# AMS_Slave_Balancing.net
KiCad netlist of a schematic drawn in Altium Designer
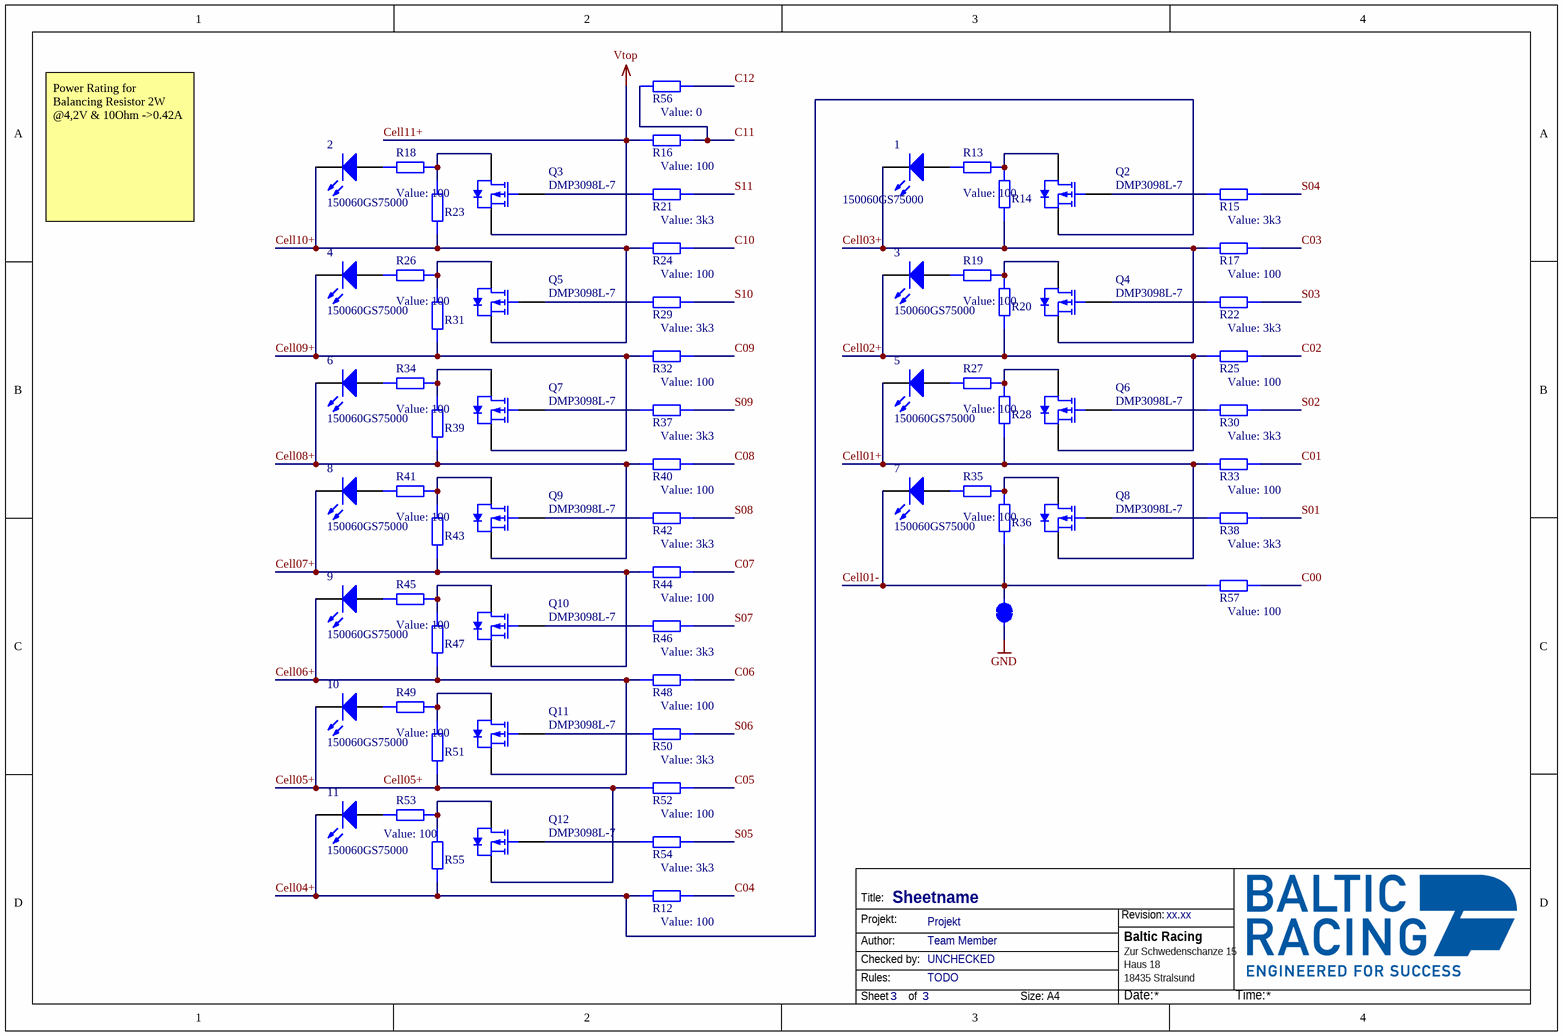
[diagram p0: AMS_Slave_Balancing.SchDoc]

(export (version "E")
  (design (tool "Eeschema 10.0.6"))
  (components
    (comp (ref "1")
      (value "150060GS75000")
      (footprint "0603_A")
      (description "SMD mono-color Chip LED, WL-SMCW, Green")
      (fields (field (name "MANUFACTURER") "Wuerth Elektronik"))
      (libsource (lib "Altium Content Vault") (part "WE-LED_K1A2-2"))
    )
    (comp (ref "2")
      (value "150060GS75000")
      (footprint "0603_A")
      (description "SMD mono-color Chip LED, WL-SMCW, Green")
      (fields (field (name "MANUFACTURER") "Wuerth Elektronik"))
      (libsource (lib "Altium Content Vault") (part "WE-LED_K1A2-2"))
    )
    (comp (ref "3")
      (value "150060GS75000")
      (footprint "0603_A")
      (description "SMD mono-color Chip LED, WL-SMCW, Green")
      (fields (field (name "MANUFACTURER") "Wuerth Elektronik"))
      (libsource (lib "Altium Content Vault") (part "WE-LED_K1A2-2"))
    )
    (comp (ref "4")
      (value "150060GS75000")
      (footprint "0603_A")
      (description "SMD mono-color Chip LED, WL-SMCW, Green")
      (fields (field (name "MANUFACTURER") "Wuerth Elektronik"))
      (libsource (lib "Altium Content Vault") (part "WE-LED_K1A2-2"))
    )
    (comp (ref "5")
      (value "150060GS75000")
      (footprint "0603_A")
      (description "SMD mono-color Chip LED, WL-SMCW, Green")
      (fields (field (name "MANUFACTURER") "Wuerth Elektronik"))
      (libsource (lib "Altium Content Vault") (part "WE-LED_K1A2-2"))
    )
    (comp (ref "6")
      (value "150060GS75000")
      (footprint "0603_A")
      (description "SMD mono-color Chip LED, WL-SMCW, Green")
      (fields (field (name "MANUFACTURER") "Wuerth Elektronik"))
      (libsource (lib "Altium Content Vault") (part "WE-LED_K1A2-2"))
    )
    (comp (ref "7")
      (value "150060GS75000")
      (footprint "0603_A")
      (description "SMD mono-color Chip LED, WL-SMCW, Green")
      (fields (field (name "MANUFACTURER") "Wuerth Elektronik"))
      (libsource (lib "Altium Content Vault") (part "WE-LED_K1A2-2"))
    )
    (comp (ref "8")
      (value "150060GS75000")
      (footprint "0603_A")
      (description "SMD mono-color Chip LED, WL-SMCW, Green")
      (fields (field (name "MANUFACTURER") "Wuerth Elektronik"))
      (libsource (lib "Altium Content Vault") (part "WE-LED_K1A2-2"))
    )
    (comp (ref "9")
      (value "150060GS75000")
      (footprint "0603_A")
      (description "SMD mono-color Chip LED, WL-SMCW, Green")
      (fields (field (name "MANUFACTURER") "Wuerth Elektronik"))
      (libsource (lib "Altium Content Vault") (part "WE-LED_K1A2-2"))
    )
    (comp (ref "10")
      (value "150060GS75000")
      (footprint "0603_A")
      (description "SMD mono-color Chip LED, WL-SMCW, Green")
      (fields (field (name "MANUFACTURER") "Wuerth Elektronik"))
      (libsource (lib "Altium Content Vault") (part "WE-LED_K1A2-2"))
    )
    (comp (ref "11")
      (value "150060GS75000")
      (footprint "0603_A")
      (description "SMD mono-color Chip LED, WL-SMCW, Green")
      (fields (field (name "MANUFACTURER") "Wuerth Elektronik"))
      (libsource (lib "Altium Content Vault") (part "WE-LED_K1A2-2"))
    )
    (comp (ref "J5")
      (value "SMD Jumper closed")
      (footprint "SMD-JUMPER-CLOSED")
      (libsource (lib "Standardbauteile") (part "SMD Jumper closed"))
    )
    (comp (ref "Q2")
      (value "DMP3098L-7")
      (footprint "DIOD-SOT23-3_V")
      (description "P-Channel Enhancement Mode MOSFET, -30 V VDS, -55 to 155 degC, 3-Pin SOT23, RoHS, Tape and Reel")
      (fields (field (name "MANUFACTURER") "Diodes Inc"))
      (libsource (lib "Altium Content Vault") (part "DIOD-PEMOS-G1S2D3-3"))
    )
    (comp (ref "Q3")
      (value "DMP3098L-7")
      (footprint "DIOD-SOT23-3_V")
      (description "P-Channel Enhancement Mode MOSFET, -30 V VDS, -55 to 155 degC, 3-Pin SOT23, RoHS, Tape and Reel")
      (fields (field (name "MANUFACTURER") "Diodes Inc"))
      (libsource (lib "Altium Content Vault") (part "DIOD-PEMOS-G1S2D3-3"))
    )
    (comp (ref "Q4")
      (value "DMP3098L-7")
      (footprint "DIOD-SOT23-3_V")
      (description "P-Channel Enhancement Mode MOSFET, -30 V VDS, -55 to 155 degC, 3-Pin SOT23, RoHS, Tape and Reel")
      (fields (field (name "MANUFACTURER") "Diodes Inc"))
      (libsource (lib "Altium Content Vault") (part "DIOD-PEMOS-G1S2D3-3"))
    )
    (comp (ref "Q5")
      (value "DMP3098L-7")
      (footprint "DIOD-SOT23-3_V")
      (description "P-Channel Enhancement Mode MOSFET, -30 V VDS, -55 to 155 degC, 3-Pin SOT23, RoHS, Tape and Reel")
      (fields (field (name "MANUFACTURER") "Diodes Inc"))
      (libsource (lib "Altium Content Vault") (part "DIOD-PEMOS-G1S2D3-3"))
    )
    (comp (ref "Q6")
      (value "DMP3098L-7")
      (footprint "DIOD-SOT23-3_V")
      (description "P-Channel Enhancement Mode MOSFET, -30 V VDS, -55 to 155 degC, 3-Pin SOT23, RoHS, Tape and Reel")
      (fields (field (name "MANUFACTURER") "Diodes Inc"))
      (libsource (lib "Altium Content Vault") (part "DIOD-PEMOS-G1S2D3-3"))
    )
    (comp (ref "Q7")
      (value "DMP3098L-7")
      (footprint "DIOD-SOT23-3_V")
      (description "P-Channel Enhancement Mode MOSFET, -30 V VDS, -55 to 155 degC, 3-Pin SOT23, RoHS, Tape and Reel")
      (fields (field (name "MANUFACTURER") "Diodes Inc"))
      (libsource (lib "Altium Content Vault") (part "DIOD-PEMOS-G1S2D3-3"))
    )
    (comp (ref "Q8")
      (value "DMP3098L-7")
      (footprint "DIOD-SOT23-3_V")
      (description "P-Channel Enhancement Mode MOSFET, -30 V VDS, -55 to 155 degC, 3-Pin SOT23, RoHS, Tape and Reel")
      (fields (field (name "MANUFACTURER") "Diodes Inc"))
      (libsource (lib "Altium Content Vault") (part "DIOD-PEMOS-G1S2D3-3"))
    )
    (comp (ref "Q9")
      (value "DMP3098L-7")
      (footprint "DIOD-SOT23-3_V")
      (description "P-Channel Enhancement Mode MOSFET, -30 V VDS, -55 to 155 degC, 3-Pin SOT23, RoHS, Tape and Reel")
      (fields (field (name "MANUFACTURER") "Diodes Inc"))
      (libsource (lib "Altium Content Vault") (part "DIOD-PEMOS-G1S2D3-3"))
    )
    (comp (ref "Q10")
      (value "DMP3098L-7")
      (footprint "DIOD-SOT23-3_V")
      (description "P-Channel Enhancement Mode MOSFET, -30 V VDS, -55 to 155 degC, 3-Pin SOT23, RoHS, Tape and Reel")
      (fields (field (name "MANUFACTURER") "Diodes Inc"))
      (libsource (lib "Altium Content Vault") (part "DIOD-PEMOS-G1S2D3-3"))
    )
    (comp (ref "Q11")
      (value "DMP3098L-7")
      (footprint "DIOD-SOT23-3_V")
      (description "P-Channel Enhancement Mode MOSFET, -30 V VDS, -55 to 155 degC, 3-Pin SOT23, RoHS, Tape and Reel")
      (fields (field (name "MANUFACTURER") "Diodes Inc"))
      (libsource (lib "Altium Content Vault") (part "DIOD-PEMOS-G1S2D3-3"))
    )
    (comp (ref "Q12")
      (value "DMP3098L-7")
      (footprint "DIOD-SOT23-3_V")
      (description "P-Channel Enhancement Mode MOSFET, -30 V VDS, -55 to 155 degC, 3-Pin SOT23, RoHS, Tape and Reel")
      (fields (field (name "MANUFACTURER") "Diodes Inc"))
      (libsource (lib "Altium Content Vault") (part "DIOD-PEMOS-G1S2D3-3"))
    )
    (comp (ref "R12")
      (value "100")
      (footprint "STACKPOLE CSR0603")
      (description "Resistor with multiple footprints")
      (fields (field (name "Comment") "Value"))
      (libsource (lib "Standardbauteile") (part "SMD Resistor"))
    )
    (comp (ref "R13")
      (value "100")
      (footprint "STACKPOLE CSR0603")
      (description "Resistor with multiple footprints")
      (fields (field (name "Comment") "SMD Resistor"))
      (libsource (lib "") (part "SMD Resistor_1"))
    )
    (comp (ref "R14")
      (value "SMD Resistor")
      (footprint "STACKPOLE CSRN2512")
      (description "Resistor with multiple footprints")
      (libsource (lib "Standardbauteile") (part "SMD Resistor"))
    )
    (comp (ref "R15")
      (value "3k3")
      (footprint "STACKPOLE CSR0603")
      (description "Resistor with multiple footprints")
      (fields (field (name "Comment") "SMD Resistor"))
      (libsource (lib "Standardbauteile") (part "SMD Resistor"))
    )
    (comp (ref "R16")
      (value "100")
      (footprint "STACKPOLE CSR0603")
      (description "Resistor with multiple footprints")
      (fields (field (name "Comment") "Value"))
      (libsource (lib "Standardbauteile") (part "SMD Resistor"))
    )
    (comp (ref "R17")
      (value "100")
      (footprint "STACKPOLE CSR0603")
      (description "Resistor with multiple footprints")
      (fields (field (name "Comment") "Value"))
      (libsource (lib "Standardbauteile") (part "SMD Resistor"))
    )
    (comp (ref "R18")
      (value "100")
      (footprint "STACKPOLE CSR0603")
      (description "Resistor with multiple footprints")
      (fields (field (name "Comment") "SMD Resistor"))
      (libsource (lib "") (part "SMD Resistor_1"))
    )
    (comp (ref "R19")
      (value "100")
      (footprint "STACKPOLE CSR0603")
      (description "Resistor with multiple footprints")
      (fields (field (name "Comment") "SMD Resistor"))
      (libsource (lib "") (part "SMD Resistor_1"))
    )
    (comp (ref "R20")
      (value "SMD Resistor")
      (footprint "STACKPOLE CSRN2512")
      (description "Resistor with multiple footprints")
      (libsource (lib "Standardbauteile") (part "SMD Resistor"))
    )
    (comp (ref "R21")
      (value "3k3")
      (footprint "STACKPOLE CSR0603")
      (description "Resistor with multiple footprints")
      (fields (field (name "Comment") "SMD Resistor"))
      (libsource (lib "Standardbauteile") (part "SMD Resistor"))
    )
    (comp (ref "R22")
      (value "3k3")
      (footprint "STACKPOLE CSR0603")
      (description "Resistor with multiple footprints")
      (fields (field (name "Comment") "SMD Resistor"))
      (libsource (lib "Standardbauteile") (part "SMD Resistor"))
    )
    (comp (ref "R23")
      (value "SMD Resistor")
      (footprint "STACKPOLE CSRN2512")
      (description "Resistor with multiple footprints")
      (libsource (lib "Standardbauteile") (part "SMD Resistor"))
    )
    (comp (ref "R24")
      (value "100")
      (footprint "STACKPOLE CSR0603")
      (description "Resistor with multiple footprints")
      (fields (field (name "Comment") "Value"))
      (libsource (lib "Standardbauteile") (part "SMD Resistor"))
    )
    (comp (ref "R25")
      (value "100")
      (footprint "STACKPOLE CSR0603")
      (description "Resistor with multiple footprints")
      (fields (field (name "Comment") "Value"))
      (libsource (lib "Standardbauteile") (part "SMD Resistor"))
    )
    (comp (ref "R26")
      (value "100")
      (footprint "STACKPOLE CSR0603")
      (description "Resistor with multiple footprints")
      (fields (field (name "Comment") "SMD Resistor"))
      (libsource (lib "") (part "SMD Resistor_1"))
    )
    (comp (ref "R27")
      (value "100")
      (footprint "STACKPOLE CSR0603")
      (description "Resistor with multiple footprints")
      (fields (field (name "Comment") "SMD Resistor"))
      (libsource (lib "") (part "SMD Resistor_1"))
    )
    (comp (ref "R28")
      (value "SMD Resistor")
      (footprint "STACKPOLE CSRN2512")
      (description "Resistor with multiple footprints")
      (libsource (lib "Standardbauteile") (part "SMD Resistor"))
    )
    (comp (ref "R29")
      (value "3k3")
      (footprint "STACKPOLE CSR0603")
      (description "Resistor with multiple footprints")
      (fields (field (name "Comment") "SMD Resistor"))
      (libsource (lib "Standardbauteile") (part "SMD Resistor"))
    )
    (comp (ref "R30")
      (value "3k3")
      (footprint "STACKPOLE CSR0603")
      (description "Resistor with multiple footprints")
      (fields (field (name "Comment") "SMD Resistor"))
      (libsource (lib "Standardbauteile") (part "SMD Resistor"))
    )
    (comp (ref "R31")
      (value "SMD Resistor")
      (footprint "STACKPOLE CSRN2512")
      (description "Resistor with multiple footprints")
      (libsource (lib "Standardbauteile") (part "SMD Resistor"))
    )
    (comp (ref "R32")
      (value "100")
      (footprint "STACKPOLE CSR0603")
      (description "Resistor with multiple footprints")
      (fields (field (name "Comment") "Value"))
      (libsource (lib "Standardbauteile") (part "SMD Resistor"))
    )
    (comp (ref "R33")
      (value "100")
      (footprint "STACKPOLE CSR0603")
      (description "Resistor with multiple footprints")
      (fields (field (name "Comment") "Value"))
      (libsource (lib "Standardbauteile") (part "SMD Resistor"))
    )
    (comp (ref "R34")
      (value "100")
      (footprint "STACKPOLE CSR0603")
      (description "Resistor with multiple footprints")
      (fields (field (name "Comment") "SMD Resistor"))
      (libsource (lib "") (part "SMD Resistor_1"))
    )
    (comp (ref "R35")
      (value "100")
      (footprint "STACKPOLE CSR0603")
      (description "Resistor with multiple footprints")
      (fields (field (name "Comment") "SMD Resistor"))
      (libsource (lib "") (part "SMD Resistor_1"))
    )
    (comp (ref "R36")
      (value "SMD Resistor")
      (footprint "STACKPOLE CSRN2512")
      (description "Resistor with multiple footprints")
      (libsource (lib "Standardbauteile") (part "SMD Resistor"))
    )
    (comp (ref "R37")
      (value "3k3")
      (footprint "STACKPOLE CSR0603")
      (description "Resistor with multiple footprints")
      (fields (field (name "Comment") "SMD Resistor"))
      (libsource (lib "Standardbauteile") (part "SMD Resistor"))
    )
    (comp (ref "R38")
      (value "3k3")
      (footprint "STACKPOLE CSR0603")
      (description "Resistor with multiple footprints")
      (fields (field (name "Comment") "SMD Resistor"))
      (libsource (lib "Standardbauteile") (part "SMD Resistor"))
    )
    (comp (ref "R39")
      (value "SMD Resistor")
      (footprint "STACKPOLE CSRN2512")
      (description "Resistor with multiple footprints")
      (libsource (lib "Standardbauteile") (part "SMD Resistor"))
    )
    (comp (ref "R40")
      (value "100")
      (footprint "STACKPOLE CSR0603")
      (description "Resistor with multiple footprints")
      (fields (field (name "Comment") "Value"))
      (libsource (lib "Standardbauteile") (part "SMD Resistor"))
    )
    (comp (ref "R41")
      (value "100")
      (footprint "STACKPOLE CSR0603")
      (description "Resistor with multiple footprints")
      (fields (field (name "Comment") "SMD Resistor"))
      (libsource (lib "") (part "SMD Resistor_1"))
    )
    (comp (ref "R42")
      (value "3k3")
      (footprint "STACKPOLE CSR0603")
      (description "Resistor with multiple footprints")
      (fields (field (name "Comment") "SMD Resistor"))
      (libsource (lib "Standardbauteile") (part "SMD Resistor"))
    )
    (comp (ref "R43")
      (value "SMD Resistor")
      (footprint "STACKPOLE CSRN2512")
      (description "Resistor with multiple footprints")
      (libsource (lib "Standardbauteile") (part "SMD Resistor"))
    )
    (comp (ref "R44")
      (value "100")
      (footprint "STACKPOLE CSR0603")
      (description "Resistor with multiple footprints")
      (fields (field (name "Comment") "Value"))
      (libsource (lib "Standardbauteile") (part "SMD Resistor"))
    )
    (comp (ref "R45")
      (value "100")
      (footprint "STACKPOLE CSR0603")
      (description "Resistor with multiple footprints")
      (fields (field (name "Comment") "SMD Resistor"))
      (libsource (lib "") (part "SMD Resistor_1"))
    )
    (comp (ref "R46")
      (value "3k3")
      (footprint "STACKPOLE CSR0603")
      (description "Resistor with multiple footprints")
      (fields (field (name "Comment") "SMD Resistor"))
      (libsource (lib "Standardbauteile") (part "SMD Resistor"))
    )
    (comp (ref "R47")
      (value "SMD Resistor")
      (footprint "STACKPOLE CSRN2512")
      (description "Resistor with multiple footprints")
      (libsource (lib "Standardbauteile") (part "SMD Resistor"))
    )
    (comp (ref "R48")
      (value "100")
      (footprint "STACKPOLE CSR0603")
      (description "Resistor with multiple footprints")
      (fields (field (name "Comment") "Value"))
      (libsource (lib "Standardbauteile") (part "SMD Resistor"))
    )
    (comp (ref "R49")
      (value "100")
      (footprint "STACKPOLE CSR0603")
      (description "Resistor with multiple footprints")
      (fields (field (name "Comment") "SMD Resistor"))
      (libsource (lib "") (part "SMD Resistor_1"))
    )
    (comp (ref "R50")
      (value "3k3")
      (footprint "STACKPOLE CSR0603")
      (description "Resistor with multiple footprints")
      (fields (field (name "Comment") "SMD Resistor"))
      (libsource (lib "Standardbauteile") (part "SMD Resistor"))
    )
    (comp (ref "R51")
      (value "SMD Resistor")
      (footprint "STACKPOLE CSRN2512")
      (description "Resistor with multiple footprints")
      (libsource (lib "Standardbauteile") (part "SMD Resistor"))
    )
    (comp (ref "R52")
      (value "100")
      (footprint "STACKPOLE CSR0603")
      (description "Resistor with multiple footprints")
      (fields (field (name "Comment") "Value"))
      (libsource (lib "Standardbauteile") (part "SMD Resistor"))
    )
    (comp (ref "R53")
      (value "100")
      (footprint "STACKPOLE CSR0603")
      (description "Resistor with multiple footprints")
      (fields (field (name "Comment") "SMD Resistor"))
      (libsource (lib "") (part "SMD Resistor_1"))
    )
    (comp (ref "R54")
      (value "3k3")
      (footprint "STACKPOLE CSR0603")
      (description "Resistor with multiple footprints")
      (fields (field (name "Comment") "SMD Resistor"))
      (libsource (lib "Standardbauteile") (part "SMD Resistor"))
    )
    (comp (ref "R55")
      (value "SMD Resistor")
      (footprint "STACKPOLE CSRN2512")
      (description "Resistor with multiple footprints")
      (libsource (lib "Standardbauteile") (part "SMD Resistor"))
    )
    (comp (ref "R56")
      (value "0")
      (footprint "STACKPOLE CSR0603")
      (description "Resistor with multiple footprints")
      (fields (field (name "Comment") "Value"))
      (libsource (lib "Standardbauteile") (part "SMD Resistor"))
    )
    (comp (ref "R57")
      (value "100")
      (footprint "STACKPOLE CSR0603")
      (description "Resistor with multiple footprints")
      (fields (field (name "Comment") "Value"))
      (libsource (lib "Standardbauteile") (part "SMD Resistor"))
    )
  )
  (nets
    (net (code "1") (name "/C00") (class "Default")
      (node (ref "R57") (pin "2") (pinfunction "2_2") (pintype "passive"))
    )
    (net (code "2") (name "/C01") (class "Default")
      (node (ref "R33") (pin "2") (pinfunction "2_2") (pintype "passive"))
    )
    (net (code "3") (name "/C02") (class "Default")
      (node (ref "R25") (pin "2") (pinfunction "2_2") (pintype "passive"))
    )
    (net (code "4") (name "/C03") (class "Default")
      (node (ref "R17") (pin "2") (pinfunction "2_2") (pintype "passive"))
    )
    (net (code "5") (name "/C04") (class "Default")
      (node (ref "R12") (pin "2") (pinfunction "2_2") (pintype "passive"))
    )
    (net (code "6") (name "/C05") (class "Default")
      (node (ref "R52") (pin "2") (pinfunction "2_2") (pintype "passive"))
    )
    (net (code "7") (name "/C06") (class "Default")
      (node (ref "R48") (pin "2") (pinfunction "2_2") (pintype "passive"))
    )
    (net (code "8") (name "/C07") (class "Default")
      (node (ref "R44") (pin "2") (pinfunction "2_2") (pintype "passive"))
    )
    (net (code "9") (name "/C08") (class "Default")
      (node (ref "R40") (pin "2") (pinfunction "2_2") (pintype "passive"))
    )
    (net (code "10") (name "/C09") (class "Default")
      (node (ref "R32") (pin "2") (pinfunction "2_2") (pintype "passive"))
    )
    (net (code "11") (name "/C10") (class "Default")
      (node (ref "R24") (pin "2") (pinfunction "2_2") (pintype "passive"))
    )
    (net (code "12") (name "/C11") (class "Default")
      (node (ref "R16") (pin "2") (pinfunction "2_2") (pintype "passive"))
      (node (ref "R56") (pin "1") (pinfunction "1_1") (pintype "passive"))
    )
    (net (code "13") (name "/C12") (class "Default")
      (node (ref "R56") (pin "2") (pinfunction "2_2") (pintype "passive"))
    )
    (net (code "14") (name "/Cell01+") (class "Default")
      (node (ref "5") (pin "1") (pinfunction "K_1") (pintype "passive"))
      (node (ref "Q8") (pin "2") (pinfunction "S_2") (pintype "passive"))
      (node (ref "R28") (pin "1") (pinfunction "1_1") (pintype "passive"))
      (node (ref "R33") (pin "1") (pinfunction "1_1") (pintype "passive"))
    )
    (net (code "15") (name "/Cell01-") (class "Default")
      (node (ref "7") (pin "1") (pinfunction "K_1") (pintype "passive"))
      (node (ref "J5") (pin "2") (pinfunction "2_2") (pintype "passive"))
      (node (ref "R36") (pin "1") (pinfunction "1_1") (pintype "passive"))
      (node (ref "R57") (pin "1") (pinfunction "1_1") (pintype "passive"))
    )
    (net (code "16") (name "/Cell02+") (class "Default")
      (node (ref "3") (pin "1") (pinfunction "K_1") (pintype "passive"))
      (node (ref "Q6") (pin "2") (pinfunction "S_2") (pintype "passive"))
      (node (ref "R20") (pin "1") (pinfunction "1_1") (pintype "passive"))
      (node (ref "R25") (pin "1") (pinfunction "1_1") (pintype "passive"))
    )
    (net (code "17") (name "/Cell03+") (class "Default")
      (node (ref "1") (pin "1") (pinfunction "K_1") (pintype "passive"))
      (node (ref "Q4") (pin "2") (pinfunction "S_2") (pintype "passive"))
      (node (ref "R14") (pin "1") (pinfunction "1_1") (pintype "passive"))
      (node (ref "R17") (pin "1") (pinfunction "1_1") (pintype "passive"))
    )
    (net (code "18") (name "/Cell04+") (class "Default")
      (node (ref "11") (pin "1") (pinfunction "K_1") (pintype "passive"))
      (node (ref "Q2") (pin "2") (pinfunction "S_2") (pintype "passive"))
      (node (ref "R12") (pin "1") (pinfunction "1_1") (pintype "passive"))
      (node (ref "R55") (pin "1") (pinfunction "1_1") (pintype "passive"))
    )
    (net (code "19") (name "/Cell05+") (class "Default")
      (node (ref "10") (pin "1") (pinfunction "K_1") (pintype "passive"))
      (node (ref "Q12") (pin "2") (pinfunction "S_2") (pintype "passive"))
      (node (ref "R51") (pin "1") (pinfunction "1_1") (pintype "passive"))
      (node (ref "R52") (pin "1") (pinfunction "1_1") (pintype "passive"))
    )
    (net (code "20") (name "/Cell06+") (class "Default")
      (node (ref "9") (pin "1") (pinfunction "K_1") (pintype "passive"))
      (node (ref "Q11") (pin "2") (pinfunction "S_2") (pintype "passive"))
      (node (ref "R47") (pin "1") (pinfunction "1_1") (pintype "passive"))
      (node (ref "R48") (pin "1") (pinfunction "1_1") (pintype "passive"))
    )
    (net (code "21") (name "/Cell07+") (class "Default")
      (node (ref "8") (pin "1") (pinfunction "K_1") (pintype "passive"))
      (node (ref "Q10") (pin "2") (pinfunction "S_2") (pintype "passive"))
      (node (ref "R43") (pin "1") (pinfunction "1_1") (pintype "passive"))
      (node (ref "R44") (pin "1") (pinfunction "1_1") (pintype "passive"))
    )
    (net (code "22") (name "/Cell08+") (class "Default")
      (node (ref "6") (pin "1") (pinfunction "K_1") (pintype "passive"))
      (node (ref "Q9") (pin "2") (pinfunction "S_2") (pintype "passive"))
      (node (ref "R39") (pin "1") (pinfunction "1_1") (pintype "passive"))
      (node (ref "R40") (pin "1") (pinfunction "1_1") (pintype "passive"))
    )
    (net (code "23") (name "/Cell09+") (class "Default")
      (node (ref "4") (pin "1") (pinfunction "K_1") (pintype "passive"))
      (node (ref "Q7") (pin "2") (pinfunction "S_2") (pintype "passive"))
      (node (ref "R31") (pin "1") (pinfunction "1_1") (pintype "passive"))
      (node (ref "R32") (pin "1") (pinfunction "1_1") (pintype "passive"))
    )
    (net (code "24") (name "/Cell10+") (class "Default")
      (node (ref "2") (pin "1") (pinfunction "K_1") (pintype "passive"))
      (node (ref "Q5") (pin "2") (pinfunction "S_2") (pintype "passive"))
      (node (ref "R23") (pin "1") (pinfunction "1_1") (pintype "passive"))
      (node (ref "R24") (pin "1") (pinfunction "1_1") (pintype "passive"))
    )
    (net (code "25") (name "/S01") (class "Default")
      (node (ref "R38") (pin "2") (pinfunction "2_2") (pintype "passive"))
    )
    (net (code "26") (name "/S02") (class "Default")
      (node (ref "R30") (pin "2") (pinfunction "2_2") (pintype "passive"))
    )
    (net (code "27") (name "/S03") (class "Default")
      (node (ref "R22") (pin "2") (pinfunction "2_2") (pintype "passive"))
    )
    (net (code "28") (name "/S04") (class "Default")
      (node (ref "R15") (pin "2") (pinfunction "2_2") (pintype "passive"))
    )
    (net (code "29") (name "/S05") (class "Default")
      (node (ref "R54") (pin "2") (pinfunction "2_2") (pintype "passive"))
    )
    (net (code "30") (name "/S06") (class "Default")
      (node (ref "R50") (pin "2") (pinfunction "2_2") (pintype "passive"))
    )
    (net (code "31") (name "/S07") (class "Default")
      (node (ref "R46") (pin "2") (pinfunction "2_2") (pintype "passive"))
    )
    (net (code "32") (name "/S08") (class "Default")
      (node (ref "R42") (pin "2") (pinfunction "2_2") (pintype "passive"))
    )
    (net (code "33") (name "/S09") (class "Default")
      (node (ref "R37") (pin "2") (pinfunction "2_2") (pintype "passive"))
    )
    (net (code "34") (name "/S10") (class "Default")
      (node (ref "R29") (pin "2") (pinfunction "2_2") (pintype "passive"))
    )
    (net (code "35") (name "/S11") (class "Default")
      (node (ref "R21") (pin "2") (pinfunction "2_2") (pintype "passive"))
    )
    (net (code "36") (name "GND") (class "Default")
      (node (ref "J5") (pin "1") (pinfunction "1_1") (pintype "passive"))
    )
    (net (code "37") (name "Net-(1-A)") (class "Default")
      (node (ref "1") (pin "2") (pinfunction "A_2") (pintype "passive"))
      (node (ref "R13") (pin "2") (pinfunction "2_2") (pintype "passive"))
    )
    (net (code "38") (name "Net-(2-A)") (class "Default")
      (node (ref "2") (pin "2") (pinfunction "A_2") (pintype "passive"))
      (node (ref "R18") (pin "2") (pinfunction "2_2") (pintype "passive"))
    )
    (net (code "39") (name "Net-(3-A)") (class "Default")
      (node (ref "3") (pin "2") (pinfunction "A_2") (pintype "passive"))
      (node (ref "R19") (pin "2") (pinfunction "2_2") (pintype "passive"))
    )
    (net (code "40") (name "Net-(4-A)") (class "Default")
      (node (ref "4") (pin "2") (pinfunction "A_2") (pintype "passive"))
      (node (ref "R26") (pin "2") (pinfunction "2_2") (pintype "passive"))
    )
    (net (code "41") (name "Net-(5-A)") (class "Default")
      (node (ref "5") (pin "2") (pinfunction "A_2") (pintype "passive"))
      (node (ref "R27") (pin "2") (pinfunction "2_2") (pintype "passive"))
    )
    (net (code "42") (name "Net-(6-A)") (class "Default")
      (node (ref "6") (pin "2") (pinfunction "A_2") (pintype "passive"))
      (node (ref "R34") (pin "2") (pinfunction "2_2") (pintype "passive"))
    )
    (net (code "43") (name "Net-(7-A)") (class "Default")
      (node (ref "7") (pin "2") (pinfunction "A_2") (pintype "passive"))
      (node (ref "R35") (pin "2") (pinfunction "2_2") (pintype "passive"))
    )
    (net (code "44") (name "Net-(8-A)") (class "Default")
      (node (ref "8") (pin "2") (pinfunction "A_2") (pintype "passive"))
      (node (ref "R41") (pin "2") (pinfunction "2_2") (pintype "passive"))
    )
    (net (code "45") (name "Net-(9-A)") (class "Default")
      (node (ref "9") (pin "2") (pinfunction "A_2") (pintype "passive"))
      (node (ref "R45") (pin "2") (pinfunction "2_2") (pintype "passive"))
    )
    (net (code "46") (name "Net-(10-A)") (class "Default")
      (node (ref "10") (pin "2") (pinfunction "A_2") (pintype "passive"))
      (node (ref "R49") (pin "2") (pinfunction "2_2") (pintype "passive"))
    )
    (net (code "47") (name "Net-(11-A)") (class "Default")
      (node (ref "11") (pin "2") (pinfunction "A_2") (pintype "passive"))
      (node (ref "R53") (pin "2") (pinfunction "2_2") (pintype "passive"))
    )
    (net (code "48") (name "Net-(Q2-D)") (class "Default")
      (node (ref "Q2") (pin "3") (pinfunction "D_3") (pintype "passive"))
      (node (ref "R13") (pin "1") (pinfunction "1_1") (pintype "passive"))
      (node (ref "R14") (pin "2") (pinfunction "2_2") (pintype "passive"))
    )
    (net (code "49") (name "Net-(Q2-G)") (class "Default")
      (node (ref "Q2") (pin "1") (pinfunction "G_1") (pintype "passive"))
      (node (ref "R15") (pin "1") (pinfunction "1_1") (pintype "passive"))
    )
    (net (code "50") (name "Net-(Q3-D)") (class "Default")
      (node (ref "Q3") (pin "3") (pinfunction "D_3") (pintype "passive"))
      (node (ref "R18") (pin "1") (pinfunction "1_1") (pintype "passive"))
      (node (ref "R23") (pin "2") (pinfunction "2_2") (pintype "passive"))
    )
    (net (code "51") (name "Net-(Q3-G)") (class "Default")
      (node (ref "Q3") (pin "1") (pinfunction "G_1") (pintype "passive"))
      (node (ref "R21") (pin "1") (pinfunction "1_1") (pintype "passive"))
    )
    (net (code "52") (name "Net-(Q4-D)") (class "Default")
      (node (ref "Q4") (pin "3") (pinfunction "D_3") (pintype "passive"))
      (node (ref "R19") (pin "1") (pinfunction "1_1") (pintype "passive"))
      (node (ref "R20") (pin "2") (pinfunction "2_2") (pintype "passive"))
    )
    (net (code "53") (name "Net-(Q4-G)") (class "Default")
      (node (ref "Q4") (pin "1") (pinfunction "G_1") (pintype "passive"))
      (node (ref "R22") (pin "1") (pinfunction "1_1") (pintype "passive"))
    )
    (net (code "54") (name "Net-(Q5-D)") (class "Default")
      (node (ref "Q5") (pin "3") (pinfunction "D_3") (pintype "passive"))
      (node (ref "R26") (pin "1") (pinfunction "1_1") (pintype "passive"))
      (node (ref "R31") (pin "2") (pinfunction "2_2") (pintype "passive"))
    )
    (net (code "55") (name "Net-(Q5-G)") (class "Default")
      (node (ref "Q5") (pin "1") (pinfunction "G_1") (pintype "passive"))
      (node (ref "R29") (pin "1") (pinfunction "1_1") (pintype "passive"))
    )
    (net (code "56") (name "Net-(Q6-D)") (class "Default")
      (node (ref "Q6") (pin "3") (pinfunction "D_3") (pintype "passive"))
      (node (ref "R27") (pin "1") (pinfunction "1_1") (pintype "passive"))
      (node (ref "R28") (pin "2") (pinfunction "2_2") (pintype "passive"))
    )
    (net (code "57") (name "Net-(Q6-G)") (class "Default")
      (node (ref "Q6") (pin "1") (pinfunction "G_1") (pintype "passive"))
      (node (ref "R30") (pin "1") (pinfunction "1_1") (pintype "passive"))
    )
    (net (code "58") (name "Net-(Q7-D)") (class "Default")
      (node (ref "Q7") (pin "3") (pinfunction "D_3") (pintype "passive"))
      (node (ref "R34") (pin "1") (pinfunction "1_1") (pintype "passive"))
      (node (ref "R39") (pin "2") (pinfunction "2_2") (pintype "passive"))
    )
    (net (code "59") (name "Net-(Q7-G)") (class "Default")
      (node (ref "Q7") (pin "1") (pinfunction "G_1") (pintype "passive"))
      (node (ref "R37") (pin "1") (pinfunction "1_1") (pintype "passive"))
    )
    (net (code "60") (name "Net-(Q8-D)") (class "Default")
      (node (ref "Q8") (pin "3") (pinfunction "D_3") (pintype "passive"))
      (node (ref "R35") (pin "1") (pinfunction "1_1") (pintype "passive"))
      (node (ref "R36") (pin "2") (pinfunction "2_2") (pintype "passive"))
    )
    (net (code "61") (name "Net-(Q8-G)") (class "Default")
      (node (ref "Q8") (pin "1") (pinfunction "G_1") (pintype "passive"))
      (node (ref "R38") (pin "1") (pinfunction "1_1") (pintype "passive"))
    )
    (net (code "62") (name "Net-(Q9-D)") (class "Default")
      (node (ref "Q9") (pin "3") (pinfunction "D_3") (pintype "passive"))
      (node (ref "R41") (pin "1") (pinfunction "1_1") (pintype "passive"))
      (node (ref "R43") (pin "2") (pinfunction "2_2") (pintype "passive"))
    )
    (net (code "63") (name "Net-(Q9-G)") (class "Default")
      (node (ref "Q9") (pin "1") (pinfunction "G_1") (pintype "passive"))
      (node (ref "R42") (pin "1") (pinfunction "1_1") (pintype "passive"))
    )
    (net (code "64") (name "Net-(Q10-D)") (class "Default")
      (node (ref "Q10") (pin "3") (pinfunction "D_3") (pintype "passive"))
      (node (ref "R45") (pin "1") (pinfunction "1_1") (pintype "passive"))
      (node (ref "R47") (pin "2") (pinfunction "2_2") (pintype "passive"))
    )
    (net (code "65") (name "Net-(Q10-G)") (class "Default")
      (node (ref "Q10") (pin "1") (pinfunction "G_1") (pintype "passive"))
      (node (ref "R46") (pin "1") (pinfunction "1_1") (pintype "passive"))
    )
    (net (code "66") (name "Net-(Q11-D)") (class "Default")
      (node (ref "Q11") (pin "3") (pinfunction "D_3") (pintype "passive"))
      (node (ref "R49") (pin "1") (pinfunction "1_1") (pintype "passive"))
      (node (ref "R51") (pin "2") (pinfunction "2_2") (pintype "passive"))
    )
    (net (code "67") (name "Net-(Q11-G)") (class "Default")
      (node (ref "Q11") (pin "1") (pinfunction "G_1") (pintype "passive"))
      (node (ref "R50") (pin "1") (pinfunction "1_1") (pintype "passive"))
    )
    (net (code "68") (name "Net-(Q12-D)") (class "Default")
      (node (ref "Q12") (pin "3") (pinfunction "D_3") (pintype "passive"))
      (node (ref "R53") (pin "1") (pinfunction "1_1") (pintype "passive"))
      (node (ref "R55") (pin "2") (pinfunction "2_2") (pintype "passive"))
    )
    (net (code "69") (name "Net-(Q12-G)") (class "Default")
      (node (ref "Q12") (pin "1") (pinfunction "G_1") (pintype "passive"))
      (node (ref "R54") (pin "1") (pinfunction "1_1") (pintype "passive"))
    )
    (net (code "70") (name "Vtop") (class "Default")
      (node (ref "Q3") (pin "2") (pinfunction "S_2") (pintype "passive"))
      (node (ref "R16") (pin "1") (pinfunction "1_1") (pintype "passive"))
    )
  )
)
